# ProPrj___2024-09-10.net
KiCad netlist of a schematic drawn in EasyEDA Pro
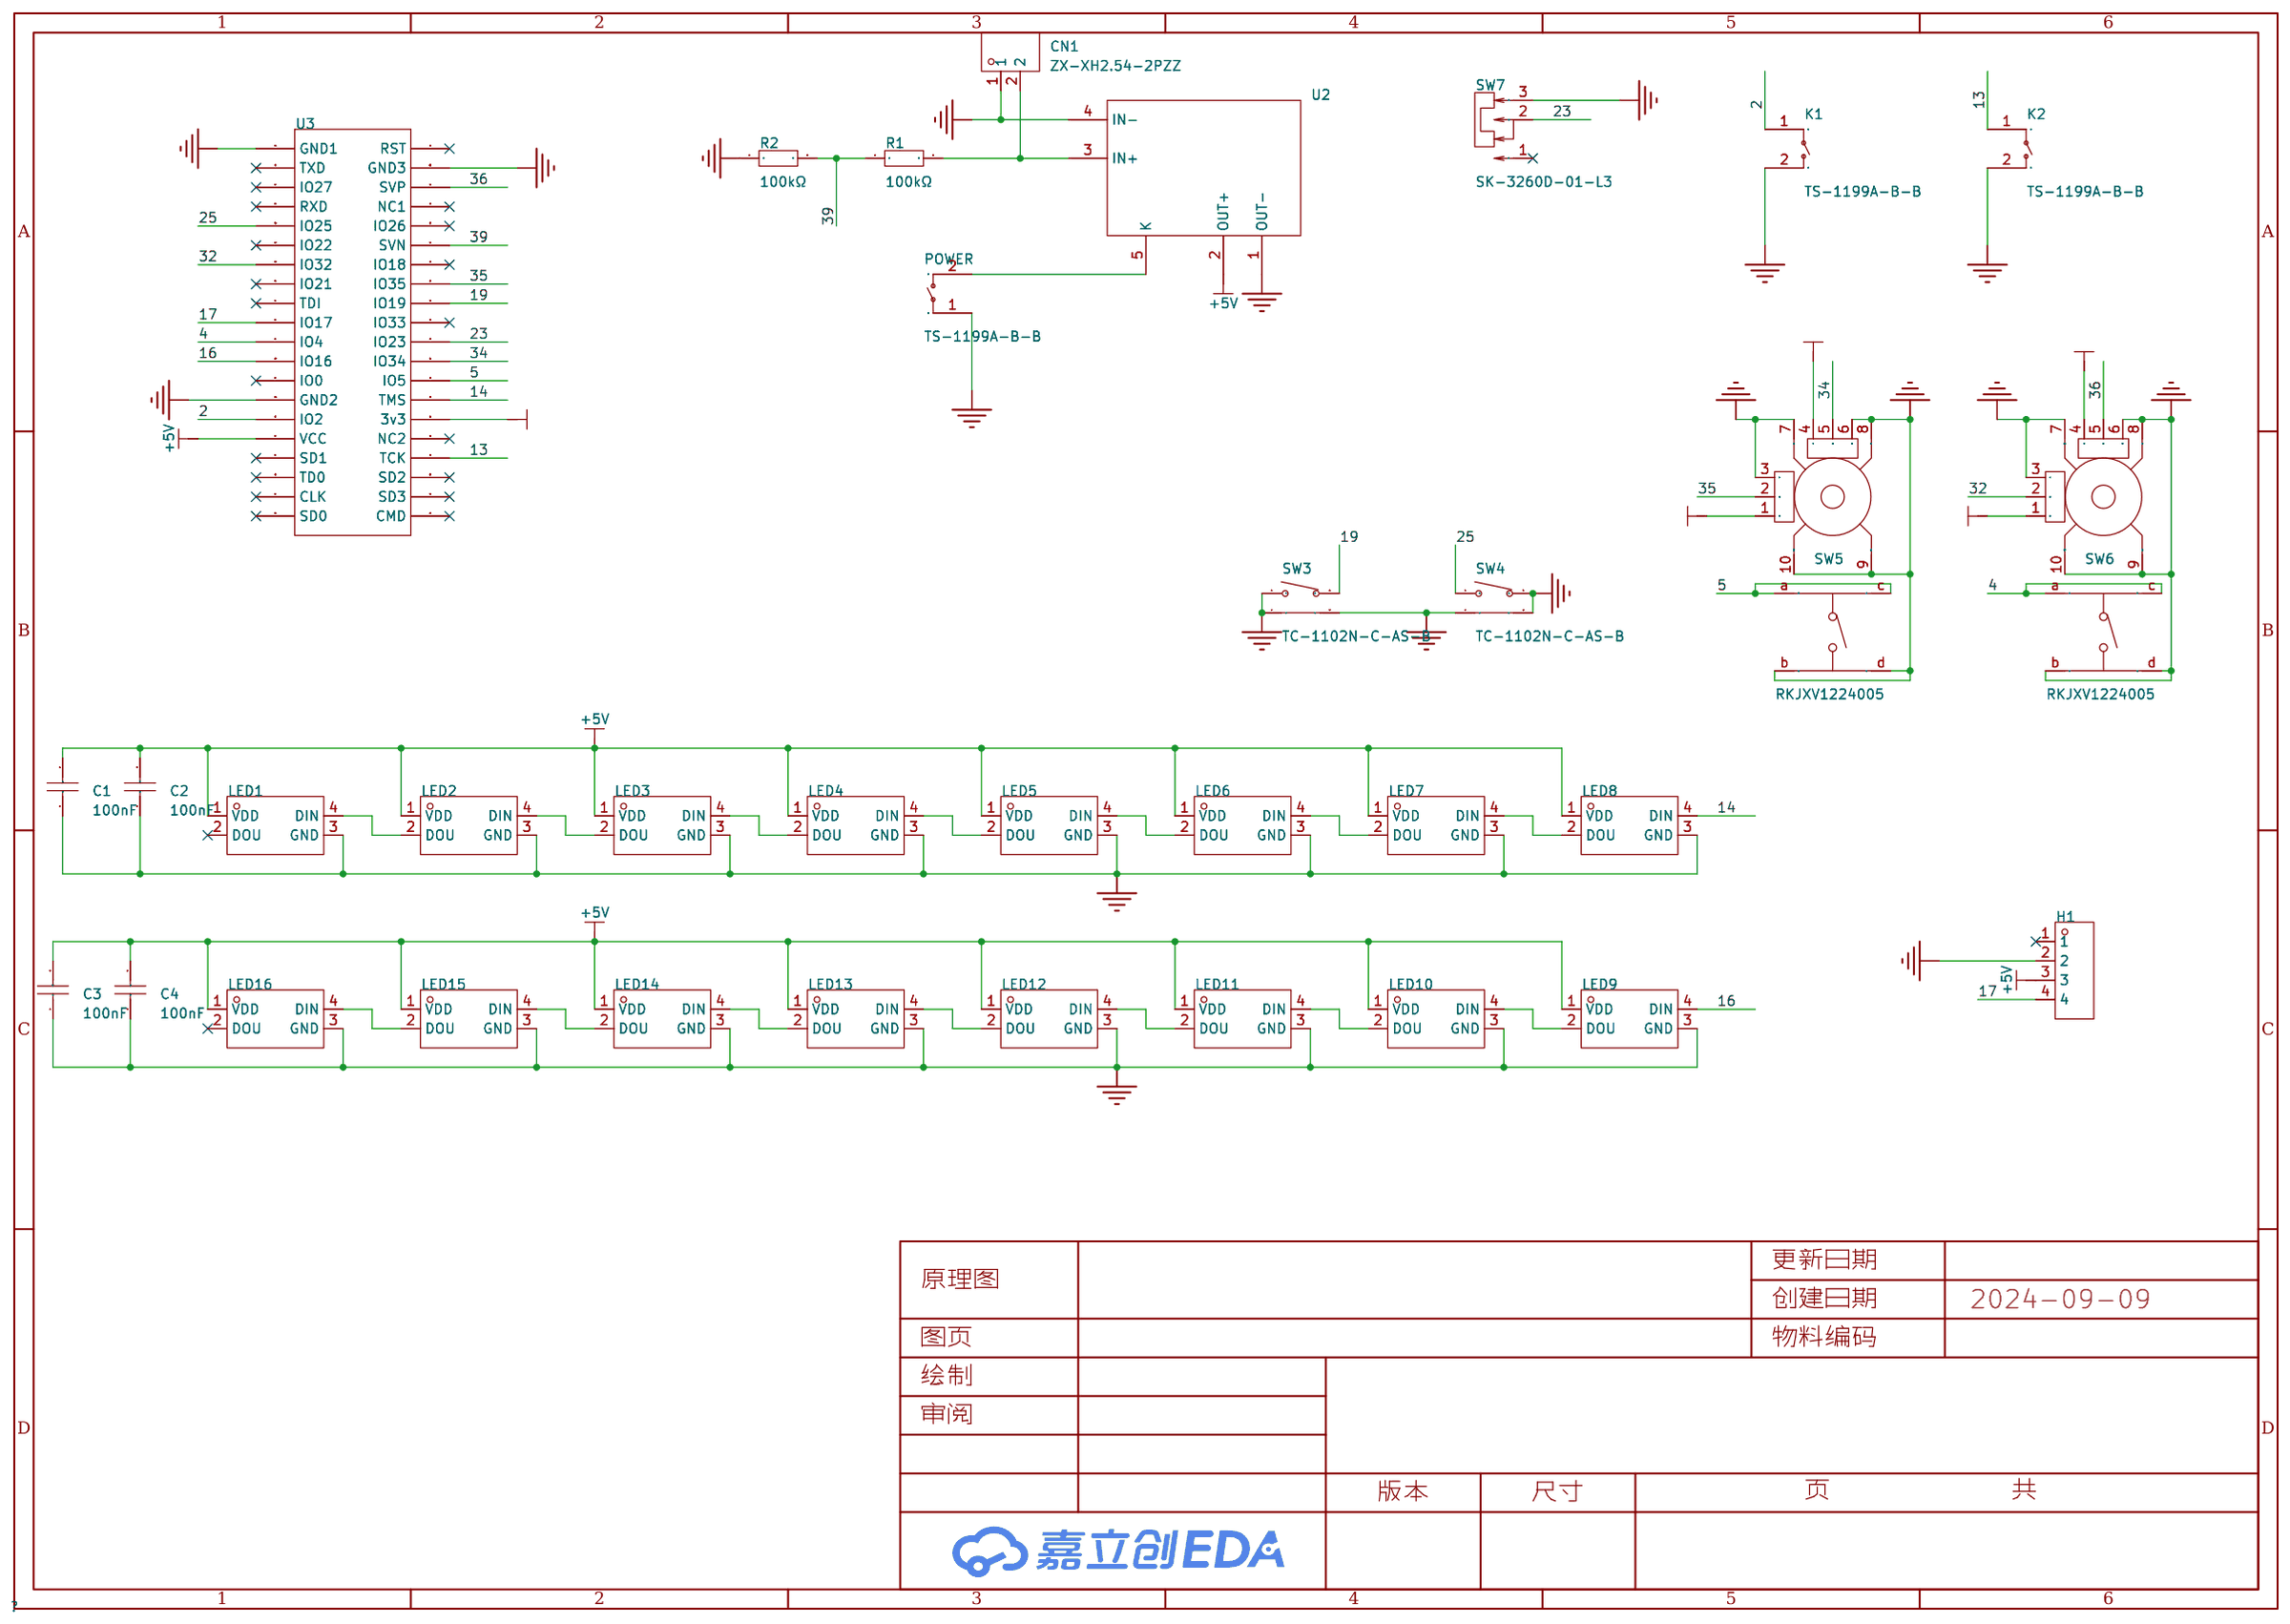
[diagram p0: schematic sheet]

(export (version "E")
  (design (tool "Eeschema 10.0.6"))
  (components
    (comp (ref "C1")
      (value "100nF")
      (footprint "easyedapro:C0805")
      (description "容值:100nF;精度:±10%;额定电压:50V;材质(温度系数):X7R;")
      (fields
        (field (name "Manufacturer Part") "CC0805KRX7R9BB104")
        (field (name "Manufacturer") "YAGEO(国巨)")
      )
      (libsource (lib "easyedapro") (part "CC0805KRX7R9BB104"))
    )
    (comp (ref "C2")
      (value "100nF")
      (footprint "easyedapro:C0805")
      (description "容值:100nF;精度:±10%;额定电压:50V;材质(温度系数):X7R;")
      (fields
        (field (name "Manufacturer Part") "CC0805KRX7R9BB104")
        (field (name "Manufacturer") "YAGEO(国巨)")
      )
      (libsource (lib "easyedapro") (part "CC0805KRX7R9BB104"))
    )
    (comp (ref "C3")
      (value "100nF")
      (footprint "easyedapro:C0805")
      (description "容值:100nF;精度:±10%;额定电压:50V;材质(温度系数):X7R;")
      (fields
        (field (name "Manufacturer Part") "CC0805KRX7R9BB104")
        (field (name "Manufacturer") "YAGEO(国巨)")
      )
      (libsource (lib "easyedapro") (part "CC0805KRX7R9BB104"))
    )
    (comp (ref "C4")
      (value "100nF")
      (footprint "easyedapro:C0805")
      (description "容值:100nF;精度:±10%;额定电压:50V;材质(温度系数):X7R;")
      (fields
        (field (name "Manufacturer Part") "CC0805KRX7R9BB104")
        (field (name "Manufacturer") "YAGEO(国巨)")
      )
      (libsource (lib "easyedapro") (part "CC0805KRX7R9BB104"))
    )
    (comp (ref "CN1")
      (value "ZX-XH2.54-2PZZ")
      (footprint "easyedapro:CONN-TH_2P-P2.50_HX25003-2A")
      (fields (field (name "Manufacturer") "Megastar(兆星)"))
      (libsource (lib "easyedapro") (part "ZX-XH2.54-2PZZ"))
    )
    (comp (ref "H1")
      (value "~")
      (footprint "easyedapro:HDR-TH_4P-P2.54-V-M")
      (libsource (lib "easyedapro") (part "PZ254V-11-04P"))
    )
    (comp (ref "K1")
      (value "TS-1199A-B-B")
      (footprint "easyedapro:SW-SMD_L6.0-W6.0-P6.00-LS6.6")
      (fields (field (name "Manufacturer") "XKB Connectivity(中国星坤)"))
      (libsource (lib "easyedapro") (part "TS-1199A-B-B"))
    )
    (comp (ref "K2")
      (value "TS-1199A-B-B")
      (footprint "easyedapro:SW-SMD_L6.0-W6.0-P6.00-LS6.6")
      (fields (field (name "Manufacturer") "XKB Connectivity(中国星坤)"))
      (libsource (lib "easyedapro") (part "TS-1199A-B-B"))
    )
    (comp (ref "LED1")
      (value "XL-5050RGBC-WS2812B")
      (footprint "easyedapro:LED-SMD_4P-L5.0-W5.0-BL_XL-5050RGBC")
      (description "5050七彩幻彩透明贴片LED灯珠 5050 幻彩透明四脚 ws2812B 内置驱动IC")
      (fields (field (name "Manufacturer") "XINGLIGHT(成兴光)"))
      (libsource (lib "easyedapro") (part "XL-5050RGBC-WS2812B"))
    )
    (comp (ref "LED2")
      (value "XL-5050RGBC-WS2812B")
      (footprint "easyedapro:LED-SMD_4P-L5.0-W5.0-BL_XL-5050RGBC")
      (description "5050七彩幻彩透明贴片LED灯珠 5050 幻彩透明四脚 ws2812B 内置驱动IC")
      (fields (field (name "Manufacturer") "XINGLIGHT(成兴光)"))
      (libsource (lib "easyedapro") (part "XL-5050RGBC-WS2812B"))
    )
    (comp (ref "LED3")
      (value "XL-5050RGBC-WS2812B")
      (footprint "easyedapro:LED-SMD_4P-L5.0-W5.0-BL_XL-5050RGBC")
      (description "5050七彩幻彩透明贴片LED灯珠 5050 幻彩透明四脚 ws2812B 内置驱动IC")
      (fields (field (name "Manufacturer") "XINGLIGHT(成兴光)"))
      (libsource (lib "easyedapro") (part "XL-5050RGBC-WS2812B"))
    )
    (comp (ref "LED4")
      (value "XL-5050RGBC-WS2812B")
      (footprint "easyedapro:LED-SMD_4P-L5.0-W5.0-BL_XL-5050RGBC")
      (description "5050七彩幻彩透明贴片LED灯珠 5050 幻彩透明四脚 ws2812B 内置驱动IC")
      (fields (field (name "Manufacturer") "XINGLIGHT(成兴光)"))
      (libsource (lib "easyedapro") (part "XL-5050RGBC-WS2812B"))
    )
    (comp (ref "LED5")
      (value "XL-5050RGBC-WS2812B")
      (footprint "easyedapro:LED-SMD_4P-L5.0-W5.0-BL_XL-5050RGBC")
      (description "5050七彩幻彩透明贴片LED灯珠 5050 幻彩透明四脚 ws2812B 内置驱动IC")
      (fields (field (name "Manufacturer") "XINGLIGHT(成兴光)"))
      (libsource (lib "easyedapro") (part "XL-5050RGBC-WS2812B"))
    )
    (comp (ref "LED6")
      (value "XL-5050RGBC-WS2812B")
      (footprint "easyedapro:LED-SMD_4P-L5.0-W5.0-BL_XL-5050RGBC")
      (description "5050七彩幻彩透明贴片LED灯珠 5050 幻彩透明四脚 ws2812B 内置驱动IC")
      (fields (field (name "Manufacturer") "XINGLIGHT(成兴光)"))
      (libsource (lib "easyedapro") (part "XL-5050RGBC-WS2812B"))
    )
    (comp (ref "LED7")
      (value "XL-5050RGBC-WS2812B")
      (footprint "easyedapro:LED-SMD_4P-L5.0-W5.0-BL_XL-5050RGBC")
      (description "5050七彩幻彩透明贴片LED灯珠 5050 幻彩透明四脚 ws2812B 内置驱动IC")
      (fields (field (name "Manufacturer") "XINGLIGHT(成兴光)"))
      (libsource (lib "easyedapro") (part "XL-5050RGBC-WS2812B"))
    )
    (comp (ref "LED8")
      (value "XL-5050RGBC-WS2812B")
      (footprint "easyedapro:LED-SMD_4P-L5.0-W5.0-BL_XL-5050RGBC")
      (description "5050七彩幻彩透明贴片LED灯珠 5050 幻彩透明四脚 ws2812B 内置驱动IC")
      (fields (field (name "Manufacturer") "XINGLIGHT(成兴光)"))
      (libsource (lib "easyedapro") (part "XL-5050RGBC-WS2812B"))
    )
    (comp (ref "LED9")
      (value "XL-5050RGBC-WS2812B")
      (footprint "easyedapro:LED-SMD_4P-L5.0-W5.0-BL_XL-5050RGBC")
      (description "5050七彩幻彩透明贴片LED灯珠 5050 幻彩透明四脚 ws2812B 内置驱动IC")
      (fields (field (name "Manufacturer") "XINGLIGHT(成兴光)"))
      (libsource (lib "easyedapro") (part "XL-5050RGBC-WS2812B"))
    )
    (comp (ref "LED10")
      (value "XL-5050RGBC-WS2812B")
      (footprint "easyedapro:LED-SMD_4P-L5.0-W5.0-BL_XL-5050RGBC")
      (description "5050七彩幻彩透明贴片LED灯珠 5050 幻彩透明四脚 ws2812B 内置驱动IC")
      (fields (field (name "Manufacturer") "XINGLIGHT(成兴光)"))
      (libsource (lib "easyedapro") (part "XL-5050RGBC-WS2812B"))
    )
    (comp (ref "LED11")
      (value "XL-5050RGBC-WS2812B")
      (footprint "easyedapro:LED-SMD_4P-L5.0-W5.0-BL_XL-5050RGBC")
      (description "5050七彩幻彩透明贴片LED灯珠 5050 幻彩透明四脚 ws2812B 内置驱动IC")
      (fields (field (name "Manufacturer") "XINGLIGHT(成兴光)"))
      (libsource (lib "easyedapro") (part "XL-5050RGBC-WS2812B"))
    )
    (comp (ref "LED12")
      (value "XL-5050RGBC-WS2812B")
      (footprint "easyedapro:LED-SMD_4P-L5.0-W5.0-BL_XL-5050RGBC")
      (description "5050七彩幻彩透明贴片LED灯珠 5050 幻彩透明四脚 ws2812B 内置驱动IC")
      (fields (field (name "Manufacturer") "XINGLIGHT(成兴光)"))
      (libsource (lib "easyedapro") (part "XL-5050RGBC-WS2812B"))
    )
    (comp (ref "LED13")
      (value "XL-5050RGBC-WS2812B")
      (footprint "easyedapro:LED-SMD_4P-L5.0-W5.0-BL_XL-5050RGBC")
      (description "5050七彩幻彩透明贴片LED灯珠 5050 幻彩透明四脚 ws2812B 内置驱动IC")
      (fields (field (name "Manufacturer") "XINGLIGHT(成兴光)"))
      (libsource (lib "easyedapro") (part "XL-5050RGBC-WS2812B"))
    )
    (comp (ref "LED14")
      (value "XL-5050RGBC-WS2812B")
      (footprint "easyedapro:LED-SMD_4P-L5.0-W5.0-BL_XL-5050RGBC")
      (description "5050七彩幻彩透明贴片LED灯珠 5050 幻彩透明四脚 ws2812B 内置驱动IC")
      (fields (field (name "Manufacturer") "XINGLIGHT(成兴光)"))
      (libsource (lib "easyedapro") (part "XL-5050RGBC-WS2812B"))
    )
    (comp (ref "LED15")
      (value "XL-5050RGBC-WS2812B")
      (footprint "easyedapro:LED-SMD_4P-L5.0-W5.0-BL_XL-5050RGBC")
      (description "5050七彩幻彩透明贴片LED灯珠 5050 幻彩透明四脚 ws2812B 内置驱动IC")
      (fields (field (name "Manufacturer") "XINGLIGHT(成兴光)"))
      (libsource (lib "easyedapro") (part "XL-5050RGBC-WS2812B"))
    )
    (comp (ref "LED16")
      (value "XL-5050RGBC-WS2812B")
      (footprint "easyedapro:LED-SMD_4P-L5.0-W5.0-BL_XL-5050RGBC")
      (description "5050七彩幻彩透明贴片LED灯珠 5050 幻彩透明四脚 ws2812B 内置驱动IC")
      (fields (field (name "Manufacturer") "XINGLIGHT(成兴光)"))
      (libsource (lib "easyedapro") (part "XL-5050RGBC-WS2812B"))
    )
    (comp (ref "POWER")
      (value "TS-1199A-B-B")
      (footprint "easyedapro:SW-SMD_L6.0-W6.0-P6.00-LS6.6")
      (fields (field (name "Manufacturer") "XKB Connectivity(中国星坤)"))
      (libsource (lib "easyedapro") (part "TS-1199A-B-B"))
    )
    (comp (ref "R1")
      (value "100kΩ")
      (footprint "easyedapro:R0805")
      (description "电阻类型:厚膜电阻;阻值:100kΩ;精度:±1%;功率:125mW;最大工作电压:150V;温度系数:±100ppm/°C;")
      (fields
        (field (name "Manufacturer Part") "0805W8F1003T5E")
        (field (name "Manufacturer") "UNI-ROYAL(厚声)")
      )
      (libsource (lib "easyedapro") (part "0805W8F1003T5E_C149504"))
    )
    (comp (ref "R2")
      (value "100kΩ")
      (footprint "easyedapro:R0805")
      (description "电阻类型:厚膜电阻;阻值:100kΩ;精度:±1%;功率:125mW;最大工作电压:150V;温度系数:±100ppm/°C;")
      (fields
        (field (name "Manufacturer Part") "0805W8F1003T5E")
        (field (name "Manufacturer") "UNI-ROYAL(厚声)")
      )
      (libsource (lib "easyedapro") (part "0805W8F1003T5E_C149504"))
    )
    (comp (ref "SW3")
      (value "TC-1102N-C-AS-B")
      (footprint "easyedapro:SW-TH_TC-1102N-C-AS-B")
      (fields (field (name "Manufacturer") "XKB Connectivity(中国星坤)"))
      (libsource (lib "easyedapro") (part "TC-1102N-C-AS-B"))
    )
    (comp (ref "SW4")
      (value "TC-1102N-C-AS-B")
      (footprint "easyedapro:SW-TH_TC-1102N-C-AS-B")
      (fields (field (name "Manufacturer") "XKB Connectivity(中国星坤)"))
      (libsource (lib "easyedapro") (part "TC-1102N-C-AS-B"))
    )
    (comp (ref "SW5")
      (value "RKJXV1224005")
      (footprint "easyedapro:SW-TH_RKJXV1224005")
      (description "操纵杆复位 中央按动开关 适用于航模玩具遥控器电位器、3D摇杆PS4手柄游戏机、无人机摇杆电位器、工业控制器")
      (fields (field (name "Manufacturer") "ALPSALPINE(阿尔卑斯阿尔派)"))
      (libsource (lib "easyedapro") (part "RKJXV1224005"))
    )
    (comp (ref "SW6")
      (value "RKJXV1224005")
      (footprint "easyedapro:SW-TH_RKJXV1224005")
      (description "操纵杆复位 中央按动开关 适用于航模玩具遥控器电位器、3D摇杆PS4手柄游戏机、无人机摇杆电位器、工业控制器")
      (fields (field (name "Manufacturer") "ALPSALPINE(阿尔卑斯阿尔派)"))
      (libsource (lib "easyedapro") (part "RKJXV1224005"))
    )
    (comp (ref "SW7")
      (value "SK-3260D-01-L3")
      (footprint "easyedapro:SW-TH_SK-3260D-01-LX")
      (description "电路结构:单刀双掷;安装方式:侧插;开关颜色:黑色;额定电流(DC):50mA;额定电压(DC):12V;额定电流(AC):50mA;额定电压(AC):12V;机械寿命:1万次;")
      (fields (field (name "Manufacturer") "XKB Connectivity(中国星坤)"))
      (libsource (lib "easyedapro") (part "SK-3260D-01-L3"))
    )
    (comp (ref "U2") (value "~") (footprint "easyedapro:5V模块") (libsource (lib "easyedapro") (part "5V模块")))
    (comp (ref "U3")
      (value "~")
      (footprint "easyedapro:ESP32MINIKIT")
      (libsource (lib "easyedapro") (part "esp32minikit"))
    )
  )
  (nets
    (net (code "1") (name "+5V") (class "Default")
      (node (ref "C1") (pin "2") (pinfunction "2_2") (pintype "input"))
      (node (ref "C2") (pin "2") (pinfunction "2_2") (pintype "input"))
      (node (ref "C3") (pin "2") (pinfunction "2_2") (pintype "input"))
      (node (ref "C4") (pin "2") (pinfunction "2_2") (pintype "input"))
      (node (ref "H1") (pin "3") (pinfunction "3_3") (pintype "unspecified"))
      (node (ref "LED1") (pin "1") (pinfunction "VDD_1") (pintype "unspecified"))
      (node (ref "LED10") (pin "1") (pinfunction "VDD_1") (pintype "unspecified"))
      (node (ref "LED11") (pin "1") (pinfunction "VDD_1") (pintype "unspecified"))
      (node (ref "LED12") (pin "1") (pinfunction "VDD_1") (pintype "unspecified"))
      (node (ref "LED13") (pin "1") (pinfunction "VDD_1") (pintype "unspecified"))
      (node (ref "LED14") (pin "1") (pinfunction "VDD_1") (pintype "unspecified"))
      (node (ref "LED15") (pin "1") (pinfunction "VDD_1") (pintype "unspecified"))
      (node (ref "LED16") (pin "1") (pinfunction "VDD_1") (pintype "unspecified"))
      (node (ref "LED2") (pin "1") (pinfunction "VDD_1") (pintype "unspecified"))
      (node (ref "LED3") (pin "1") (pinfunction "VDD_1") (pintype "unspecified"))
      (node (ref "LED4") (pin "1") (pinfunction "VDD_1") (pintype "unspecified"))
      (node (ref "LED5") (pin "1") (pinfunction "VDD_1") (pintype "unspecified"))
      (node (ref "LED6") (pin "1") (pinfunction "VDD_1") (pintype "unspecified"))
      (node (ref "LED7") (pin "1") (pinfunction "VDD_1") (pintype "unspecified"))
      (node (ref "LED8") (pin "1") (pinfunction "VDD_1") (pintype "unspecified"))
      (node (ref "LED9") (pin "1") (pinfunction "VDD_1") (pintype "unspecified"))
      (node (ref "U2") (pin "2") (pinfunction "OUT+_2") (pintype "input"))
      (node (ref "U3") (pin "VCC") (pinfunction "VCC_VCC") (pintype "input"))
    )
    (net (code "2") (name "/2") (class "Default")
      (node (ref "K1") (pin "1") (pinfunction "1_1") (pintype "input"))
      (node (ref "U3") (pin "IO2") (pinfunction "IO2_IO2") (pintype "input"))
    )
    (net (code "3") (name "/4") (class "Default")
      (node (ref "SW6") (pin "a") (pinfunction "a_a") (pintype "unspecified"))
      (node (ref "SW6") (pin "c") (pinfunction "c_c") (pintype "unspecified"))
      (node (ref "U3") (pin "IO4") (pinfunction "IO4_IO4") (pintype "input"))
    )
    (net (code "4") (name "/5") (class "Default")
      (node (ref "SW5") (pin "a") (pinfunction "a_a") (pintype "unspecified"))
      (node (ref "SW5") (pin "c") (pinfunction "c_c") (pintype "unspecified"))
      (node (ref "U3") (pin "IO5") (pinfunction "IO5_IO5") (pintype "input"))
    )
    (net (code "5") (name "/13") (class "Default")
      (node (ref "K2") (pin "1") (pinfunction "1_1") (pintype "input"))
      (node (ref "U3") (pin "TCK") (pinfunction "TCK_TCK") (pintype "input"))
    )
    (net (code "6") (name "/14") (class "Default")
      (node (ref "LED8") (pin "4") (pinfunction "DIN_4") (pintype "unspecified"))
      (node (ref "U3") (pin "TMS") (pinfunction "TMS_TMS") (pintype "input"))
    )
    (net (code "7") (name "/16") (class "Default")
      (node (ref "LED9") (pin "4") (pinfunction "DIN_4") (pintype "unspecified"))
      (node (ref "U3") (pin "IO16") (pinfunction "IO16_IO16") (pintype "input"))
    )
    (net (code "8") (name "/17") (class "Default")
      (node (ref "H1") (pin "4") (pinfunction "4_4") (pintype "unspecified"))
      (node (ref "U3") (pin "IO17") (pinfunction "IO17_IO17") (pintype "input"))
    )
    (net (code "9") (name "/19") (class "Default")
      (node (ref "SW3") (pin "2") (pinfunction "2_2") (pintype "input"))
      (node (ref "U3") (pin "IO19") (pinfunction "IO19_IO19") (pintype "input"))
    )
    (net (code "10") (name "/23") (class "Default")
      (node (ref "SW7") (pin "2") (pinfunction "2_2") (pintype "unspecified"))
      (node (ref "U3") (pin "IO23") (pinfunction "IO23_IO23") (pintype "input"))
    )
    (net (code "11") (name "/25") (class "Default")
      (node (ref "SW4") (pin "1") (pinfunction "1_1") (pintype "input"))
      (node (ref "U3") (pin "IO25") (pinfunction "IO25_IO25") (pintype "input"))
    )
    (net (code "12") (name "/32") (class "Default")
      (node (ref "SW6") (pin "2") (pinfunction "DTA_2") (pintype "unspecified"))
      (node (ref "U3") (pin "IO32") (pinfunction "IO32_IO32") (pintype "input"))
    )
    (net (code "13") (name "/34") (class "Default")
      (node (ref "SW5") (pin "5") (pinfunction "DTA_5") (pintype "unspecified"))
      (node (ref "U3") (pin "IO34") (pinfunction "IO34_IO34") (pintype "input"))
    )
    (net (code "14") (name "/35") (class "Default")
      (node (ref "SW5") (pin "2") (pinfunction "DTA_2") (pintype "unspecified"))
      (node (ref "U3") (pin "IO35") (pinfunction "IO35_IO35") (pintype "input"))
    )
    (net (code "15") (name "/36") (class "Default")
      (node (ref "SW6") (pin "5") (pinfunction "DTA_5") (pintype "unspecified"))
      (node (ref "U3") (pin "SVP") (pinfunction "SVP_SVP") (pintype "input"))
    )
    (net (code "16") (name "/39") (class "Default")
      (node (ref "R1") (pin "1") (pinfunction "1_1") (pintype "unspecified"))
      (node (ref "R2") (pin "2") (pinfunction "2_2") (pintype "unspecified"))
      (node (ref "U3") (pin "SVN") (pinfunction "SVN_SVN") (pintype "input"))
    )
    (net (code "17") (name "3.3V") (class "Default")
      (node (ref "SW5") (pin "1") (pinfunction "B_1") (pintype "unspecified"))
      (node (ref "SW5") (pin "4") (pinfunction "A_4") (pintype "unspecified"))
      (node (ref "SW6") (pin "1") (pinfunction "B_1") (pintype "unspecified"))
      (node (ref "SW6") (pin "4") (pinfunction "A_4") (pintype "unspecified"))
      (node (ref "U3") (pin "3v3") (pinfunction "3v3_3v3") (pintype "input"))
    )
    (net (code "18") (name "GND") (class "Default")
      (node (ref "C1") (pin "1") (pinfunction "1_1") (pintype "input"))
      (node (ref "C2") (pin "1") (pinfunction "1_1") (pintype "input"))
      (node (ref "C3") (pin "1") (pinfunction "1_1") (pintype "input"))
      (node (ref "C4") (pin "1") (pinfunction "1_1") (pintype "input"))
      (node (ref "CN1") (pin "1") (pinfunction "1_1") (pintype "unspecified"))
      (node (ref "H1") (pin "2") (pinfunction "2_2") (pintype "unspecified"))
      (node (ref "K1") (pin "2") (pinfunction "2_2") (pintype "input"))
      (node (ref "K2") (pin "2") (pinfunction "2_2") (pintype "input"))
      (node (ref "LED1") (pin "3") (pinfunction "GND_3") (pintype "unspecified"))
      (node (ref "LED10") (pin "3") (pinfunction "GND_3") (pintype "unspecified"))
      (node (ref "LED11") (pin "3") (pinfunction "GND_3") (pintype "unspecified"))
      (node (ref "LED12") (pin "3") (pinfunction "GND_3") (pintype "unspecified"))
      (node (ref "LED13") (pin "3") (pinfunction "GND_3") (pintype "unspecified"))
      (node (ref "LED14") (pin "3") (pinfunction "GND_3") (pintype "unspecified"))
      (node (ref "LED15") (pin "3") (pinfunction "GND_3") (pintype "unspecified"))
      (node (ref "LED16") (pin "3") (pinfunction "GND_3") (pintype "unspecified"))
      (node (ref "LED2") (pin "3") (pinfunction "GND_3") (pintype "unspecified"))
      (node (ref "LED3") (pin "3") (pinfunction "GND_3") (pintype "unspecified"))
      (node (ref "LED4") (pin "3") (pinfunction "GND_3") (pintype "unspecified"))
      (node (ref "LED5") (pin "3") (pinfunction "GND_3") (pintype "unspecified"))
      (node (ref "LED6") (pin "3") (pinfunction "GND_3") (pintype "unspecified"))
      (node (ref "LED7") (pin "3") (pinfunction "GND_3") (pintype "unspecified"))
      (node (ref "LED8") (pin "3") (pinfunction "GND_3") (pintype "unspecified"))
      (node (ref "LED9") (pin "3") (pinfunction "GND_3") (pintype "unspecified"))
      (node (ref "POWER") (pin "1") (pinfunction "1_1") (pintype "input"))
      (node (ref "R2") (pin "1") (pinfunction "1_1") (pintype "unspecified"))
      (node (ref "SW3") (pin "1") (pinfunction "1_1") (pintype "input"))
      (node (ref "SW3") (pin "3") (pinfunction "3_3") (pintype "input"))
      (node (ref "SW3") (pin "4") (pinfunction "4_4") (pintype "input"))
      (node (ref "SW4") (pin "2") (pinfunction "2_2") (pintype "input"))
      (node (ref "SW4") (pin "3") (pinfunction "3_3") (pintype "input"))
      (node (ref "SW4") (pin "4") (pinfunction "4_4") (pintype "input"))
      (node (ref "SW5") (pin "10") (pinfunction "GND_10") (pintype "unspecified"))
      (node (ref "SW5") (pin "3") (pinfunction "A_3") (pintype "unspecified"))
      (node (ref "SW5") (pin "6") (pinfunction "B_6") (pintype "unspecified"))
      (node (ref "SW5") (pin "7") (pinfunction "GND_7") (pintype "unspecified"))
      (node (ref "SW5") (pin "8") (pinfunction "GND_8") (pintype "unspecified"))
      (node (ref "SW5") (pin "9") (pinfunction "GND_9") (pintype "unspecified"))
      (node (ref "SW5") (pin "b") (pinfunction "b_b") (pintype "unspecified"))
      (node (ref "SW5") (pin "d") (pinfunction "d_d") (pintype "unspecified"))
      (node (ref "SW6") (pin "10") (pinfunction "GND_10") (pintype "unspecified"))
      (node (ref "SW6") (pin "3") (pinfunction "A_3") (pintype "unspecified"))
      (node (ref "SW6") (pin "6") (pinfunction "B_6") (pintype "unspecified"))
      (node (ref "SW6") (pin "7") (pinfunction "GND_7") (pintype "unspecified"))
      (node (ref "SW6") (pin "8") (pinfunction "GND_8") (pintype "unspecified"))
      (node (ref "SW6") (pin "9") (pinfunction "GND_9") (pintype "unspecified"))
      (node (ref "SW6") (pin "b") (pinfunction "b_b") (pintype "unspecified"))
      (node (ref "SW6") (pin "d") (pinfunction "d_d") (pintype "unspecified"))
      (node (ref "SW7") (pin "3") (pinfunction "3_3") (pintype "unspecified"))
      (node (ref "U2") (pin "1") (pinfunction "OUT-_1") (pintype "input"))
      (node (ref "U2") (pin "4") (pinfunction "IN-_4") (pintype "input"))
      (node (ref "U3") (pin "GND1") (pinfunction "GND1_GND1") (pintype "input"))
      (node (ref "U3") (pin "GND2") (pinfunction "GND2_GND2") (pintype "input"))
      (node (ref "U3") (pin "GND3") (pinfunction "GND3_GND3") (pintype "input"))
    )
    (net (code "19") (name "Net-(LED1-DIN)") (class "Default")
      (node (ref "LED1") (pin "4") (pinfunction "DIN_4") (pintype "unspecified"))
      (node (ref "LED2") (pin "2") (pinfunction "DOU_2") (pintype "unspecified"))
    )
    (net (code "20") (name "Net-(LED2-DIN)") (class "Default")
      (node (ref "LED2") (pin "4") (pinfunction "DIN_4") (pintype "unspecified"))
      (node (ref "LED3") (pin "2") (pinfunction "DOU_2") (pintype "unspecified"))
    )
    (net (code "21") (name "Net-(LED3-DIN)") (class "Default")
      (node (ref "LED3") (pin "4") (pinfunction "DIN_4") (pintype "unspecified"))
      (node (ref "LED4") (pin "2") (pinfunction "DOU_2") (pintype "unspecified"))
    )
    (net (code "22") (name "Net-(LED4-DIN)") (class "Default")
      (node (ref "LED4") (pin "4") (pinfunction "DIN_4") (pintype "unspecified"))
      (node (ref "LED5") (pin "2") (pinfunction "DOU_2") (pintype "unspecified"))
    )
    (net (code "23") (name "Net-(LED5-DIN)") (class "Default")
      (node (ref "LED5") (pin "4") (pinfunction "DIN_4") (pintype "unspecified"))
      (node (ref "LED6") (pin "2") (pinfunction "DOU_2") (pintype "unspecified"))
    )
    (net (code "24") (name "Net-(LED6-DIN)") (class "Default")
      (node (ref "LED6") (pin "4") (pinfunction "DIN_4") (pintype "unspecified"))
      (node (ref "LED7") (pin "2") (pinfunction "DOU_2") (pintype "unspecified"))
    )
    (net (code "25") (name "Net-(LED7-DIN)") (class "Default")
      (node (ref "LED7") (pin "4") (pinfunction "DIN_4") (pintype "unspecified"))
      (node (ref "LED8") (pin "2") (pinfunction "DOU_2") (pintype "unspecified"))
    )
    (net (code "26") (name "Net-(LED10-DIN)") (class "Default")
      (node (ref "LED10") (pin "4") (pinfunction "DIN_4") (pintype "unspecified"))
      (node (ref "LED9") (pin "2") (pinfunction "DOU_2") (pintype "unspecified"))
    )
    (net (code "27") (name "Net-(LED10-DOU)") (class "Default")
      (node (ref "LED10") (pin "2") (pinfunction "DOU_2") (pintype "unspecified"))
      (node (ref "LED11") (pin "4") (pinfunction "DIN_4") (pintype "unspecified"))
    )
    (net (code "28") (name "Net-(LED11-DOU)") (class "Default")
      (node (ref "LED11") (pin "2") (pinfunction "DOU_2") (pintype "unspecified"))
      (node (ref "LED12") (pin "4") (pinfunction "DIN_4") (pintype "unspecified"))
    )
    (net (code "29") (name "Net-(LED12-DOU)") (class "Default")
      (node (ref "LED12") (pin "2") (pinfunction "DOU_2") (pintype "unspecified"))
      (node (ref "LED13") (pin "4") (pinfunction "DIN_4") (pintype "unspecified"))
    )
    (net (code "30") (name "Net-(LED13-DOU)") (class "Default")
      (node (ref "LED13") (pin "2") (pinfunction "DOU_2") (pintype "unspecified"))
      (node (ref "LED14") (pin "4") (pinfunction "DIN_4") (pintype "unspecified"))
    )
    (net (code "31") (name "Net-(LED14-DOU)") (class "Default")
      (node (ref "LED14") (pin "2") (pinfunction "DOU_2") (pintype "unspecified"))
      (node (ref "LED15") (pin "4") (pinfunction "DIN_4") (pintype "unspecified"))
    )
    (net (code "32") (name "Net-(LED15-DOU)") (class "Default")
      (node (ref "LED15") (pin "2") (pinfunction "DOU_2") (pintype "unspecified"))
      (node (ref "LED16") (pin "4") (pinfunction "DIN_4") (pintype "unspecified"))
    )
    (net (code "33") (name "Net-(U2-IN+)") (class "Default")
      (node (ref "CN1") (pin "2") (pinfunction "2_2") (pintype "unspecified"))
      (node (ref "R1") (pin "2") (pinfunction "2_2") (pintype "unspecified"))
      (node (ref "U2") (pin "3") (pinfunction "IN+_3") (pintype "input"))
    )
    (net (code "34") (name "Net-(U2-K)") (class "Default")
      (node (ref "POWER") (pin "2") (pinfunction "2_2") (pintype "input"))
      (node (ref "U2") (pin "5") (pinfunction "K_5") (pintype "input"))
    )
    (net (code "35") (name "unconnected-(H1-Pad1)") (class "Default")
      (node (ref "H1") (pin "1") (pinfunction "1_1") (pintype "unspecified+no_connect"))
    )
    (net (code "36") (name "unconnected-(LED1-DOU-Pad2)") (class "Default")
      (node (ref "LED1") (pin "2") (pinfunction "DOU_2") (pintype "unspecified+no_connect"))
    )
    (net (code "37") (name "unconnected-(LED16-DOU-Pad2)") (class "Default")
      (node (ref "LED16") (pin "2") (pinfunction "DOU_2") (pintype "unspecified+no_connect"))
    )
    (net (code "38") (name "unconnected-(SW7-Pad1)") (class "Default")
      (node (ref "SW7") (pin "1") (pinfunction "1_1") (pintype "unspecified+no_connect"))
    )
    (net (code "39") (name "unconnected-(U3-PadCLK)") (class "Default")
      (node (ref "U3") (pin "CLK") (pinfunction "CLK_CLK") (pintype "input+no_connect"))
    )
    (net (code "40") (name "unconnected-(U3-PadCMD)") (class "Default")
      (node (ref "U3") (pin "CMD") (pinfunction "CMD_CMD") (pintype "input+no_connect"))
    )
    (net (code "41") (name "unconnected-(U3-PadIO0)") (class "Default")
      (node (ref "U3") (pin "IO0") (pinfunction "IO0_IO0") (pintype "input+no_connect"))
    )
    (net (code "42") (name "unconnected-(U3-PadIO18)") (class "Default")
      (node (ref "U3") (pin "IO18") (pinfunction "IO18_IO18") (pintype "input+no_connect"))
    )
    (net (code "43") (name "unconnected-(U3-PadIO21)") (class "Default")
      (node (ref "U3") (pin "IO21") (pinfunction "IO21_IO21") (pintype "input+no_connect"))
    )
    (net (code "44") (name "unconnected-(U3-PadIO22)") (class "Default")
      (node (ref "U3") (pin "IO22") (pinfunction "IO22_IO22") (pintype "input+no_connect"))
    )
    (net (code "45") (name "unconnected-(U3-PadIO26)") (class "Default")
      (node (ref "U3") (pin "IO26") (pinfunction "IO26_IO26") (pintype "input+no_connect"))
    )
    (net (code "46") (name "unconnected-(U3-PadIO27)") (class "Default")
      (node (ref "U3") (pin "IO27") (pinfunction "IO27_IO27") (pintype "input+no_connect"))
    )
    (net (code "47") (name "unconnected-(U3-PadIO33)") (class "Default")
      (node (ref "U3") (pin "IO33") (pinfunction "IO33_IO33") (pintype "input+no_connect"))
    )
    (net (code "48") (name "unconnected-(U3-PadNC1)") (class "Default")
      (node (ref "U3") (pin "NC1") (pinfunction "NC1_NC1") (pintype "input+no_connect"))
    )
    (net (code "49") (name "unconnected-(U3-PadNC2)") (class "Default")
      (node (ref "U3") (pin "NC2") (pinfunction "NC2_NC2") (pintype "input+no_connect"))
    )
    (net (code "50") (name "unconnected-(U3-PadRXD)") (class "Default")
      (node (ref "U3") (pin "RXD") (pinfunction "RXD_RXD") (pintype "input+no_connect"))
    )
    (net (code "51") (name "unconnected-(U3-PadSD0)") (class "Default")
      (node (ref "U3") (pin "SD0") (pinfunction "SD0_SD0") (pintype "input+no_connect"))
    )
    (net (code "52") (name "unconnected-(U3-PadSD1)") (class "Default")
      (node (ref "U3") (pin "SD1") (pinfunction "SD1_SD1") (pintype "input+no_connect"))
    )
    (net (code "53") (name "unconnected-(U3-PadSD2)") (class "Default")
      (node (ref "U3") (pin "SD2") (pinfunction "SD2_SD2") (pintype "input+no_connect"))
    )
    (net (code "54") (name "unconnected-(U3-PadSD3)") (class "Default")
      (node (ref "U3") (pin "SD3") (pinfunction "SD3_SD3") (pintype "input+no_connect"))
    )
    (net (code "55") (name "unconnected-(U3-PadTD0)") (class "Default")
      (node (ref "U3") (pin "TD0") (pinfunction "TD0_TD0") (pintype "input+no_connect"))
    )
    (net (code "56") (name "unconnected-(U3-PadTDI)") (class "Default")
      (node (ref "U3") (pin "TDI") (pinfunction "TDI_TDI") (pintype "input+no_connect"))
    )
    (net (code "57") (name "unconnected-(U3-PadTXD)") (class "Default")
      (node (ref "U3") (pin "TXD") (pinfunction "TXD_TXD") (pintype "input+no_connect"))
    )
    (net (code "58") (name "unconnected-(U3-RST-PadPST)") (class "Default")
      (node (ref "U3") (pin "PST") (pinfunction "RST_PST") (pintype "input+no_connect"))
    )
  )
)
